# El_Sequencer_Board.net
KiCad netlist of a schematic drawn in EAGLE
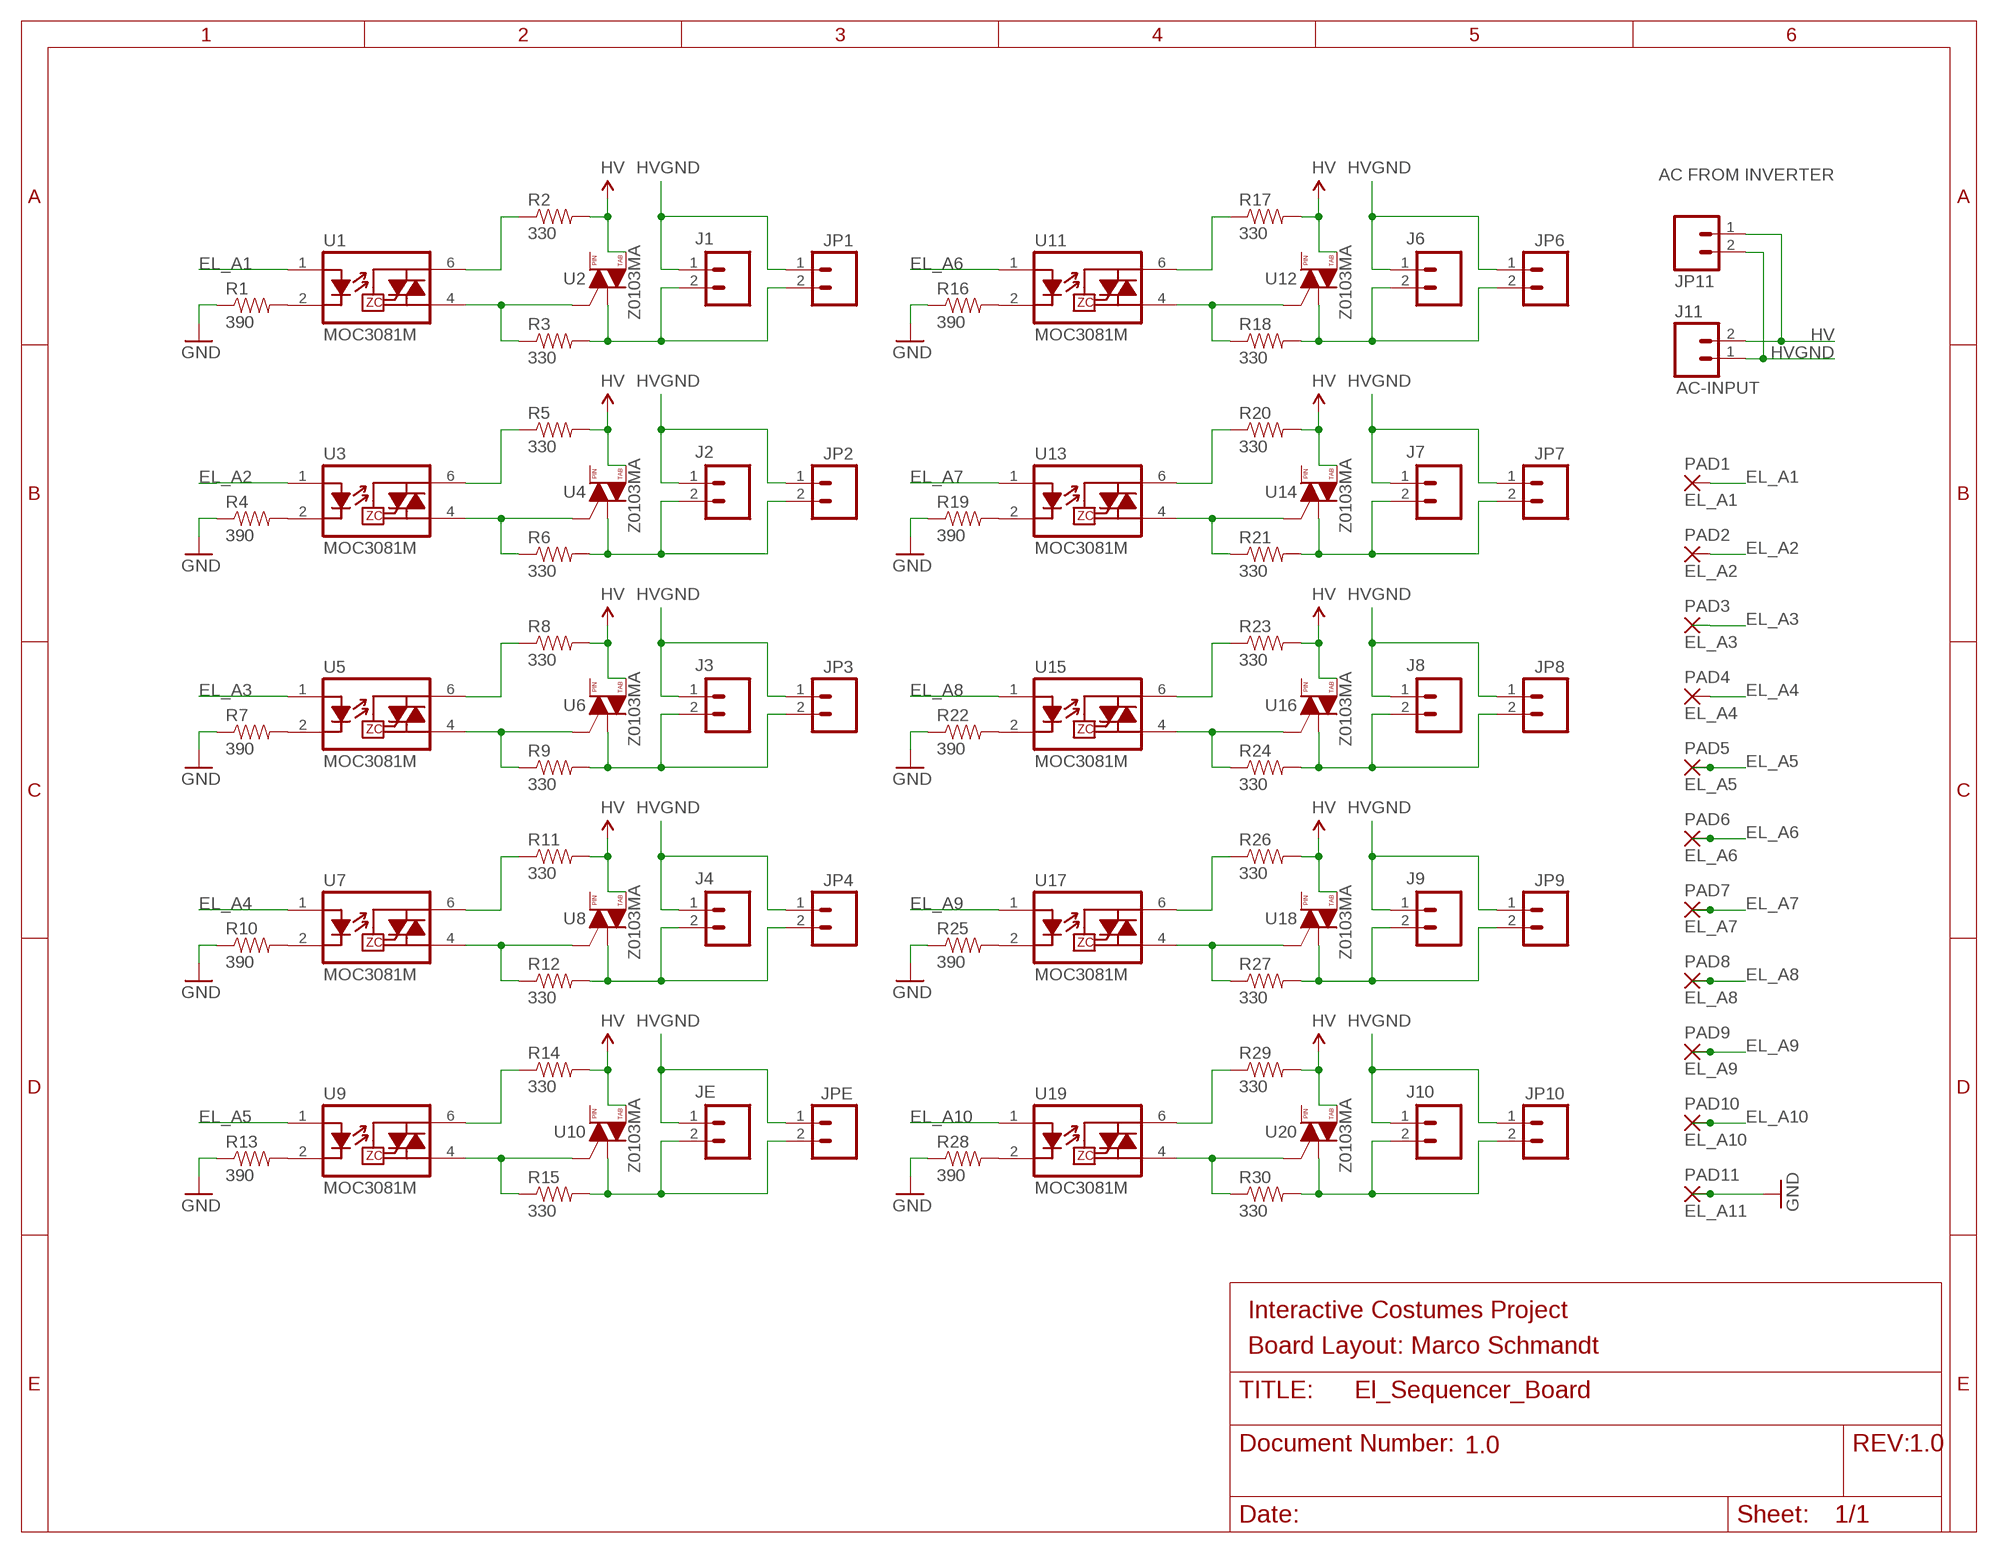
[diagram p0: schematic, sheet 1]

(export (version "E")
  (design (tool "Eeschema 10.0.6"))
  (components
    (comp (ref "J1")
      (value "M02-JST-2MM-SMT")
      (footprint "eagle-import:JST-2-SMD")
      (libsource (lib "eagle-import") (part "M02-JST-2MM-SMT"))
    )
    (comp (ref "J2")
      (value "M02-JST-2MM-SMT")
      (footprint "eagle-import:JST-2-SMD")
      (libsource (lib "eagle-import") (part "M02-JST-2MM-SMT"))
    )
    (comp (ref "J3")
      (value "M02-JST-2MM-SMT")
      (footprint "eagle-import:JST-2-SMD")
      (libsource (lib "eagle-import") (part "M02-JST-2MM-SMT"))
    )
    (comp (ref "J4")
      (value "M02-JST-2MM-SMT")
      (footprint "eagle-import:JST-2-SMD")
      (libsource (lib "eagle-import") (part "M02-JST-2MM-SMT"))
    )
    (comp (ref "J6")
      (value "M02-JST-2MM-SMT")
      (footprint "eagle-import:JST-2-SMD")
      (libsource (lib "eagle-import") (part "M02-JST-2MM-SMT"))
    )
    (comp (ref "J7")
      (value "M02-JST-2MM-SMT")
      (footprint "eagle-import:JST-2-SMD")
      (libsource (lib "eagle-import") (part "M02-JST-2MM-SMT"))
    )
    (comp (ref "J8")
      (value "M02-JST-2MM-SMT")
      (footprint "eagle-import:JST-2-SMD")
      (libsource (lib "eagle-import") (part "M02-JST-2MM-SMT"))
    )
    (comp (ref "J9")
      (value "M02-JST-2MM-SMT")
      (footprint "eagle-import:JST-2-SMD")
      (libsource (lib "eagle-import") (part "M02-JST-2MM-SMT"))
    )
    (comp (ref "J10")
      (value "M02-JST-2MM-SMT")
      (footprint "eagle-import:JST-2-SMD")
      (libsource (lib "eagle-import") (part "M02-JST-2MM-SMT"))
    )
    (comp (ref "J11")
      (value "AC-INPUT")
      (footprint "eagle-import:JST-2-SMD")
      (libsource (lib "eagle-import") (part "M02-JST-2MM-SMT"))
    )
    (comp (ref "JE")
      (value "M02-JST-2MM-SMT")
      (footprint "eagle-import:JST-2-SMD")
      (libsource (lib "eagle-import") (part "M02-JST-2MM-SMT"))
    )
    (comp (ref "JP1")
      (value "M02PTH")
      (footprint "eagle-import:1X02")
      (libsource (lib "eagle-import") (part "M02PTH"))
    )
    (comp (ref "JP2")
      (value "M02PTH")
      (footprint "eagle-import:1X02")
      (libsource (lib "eagle-import") (part "M02PTH"))
    )
    (comp (ref "JP3")
      (value "M02PTH")
      (footprint "eagle-import:1X02")
      (libsource (lib "eagle-import") (part "M02PTH"))
    )
    (comp (ref "JP4")
      (value "M02PTH")
      (footprint "eagle-import:1X02")
      (libsource (lib "eagle-import") (part "M02PTH"))
    )
    (comp (ref "JP6")
      (value "M02PTH")
      (footprint "eagle-import:1X02")
      (libsource (lib "eagle-import") (part "M02PTH"))
    )
    (comp (ref "JP7")
      (value "M02PTH")
      (footprint "eagle-import:1X02")
      (libsource (lib "eagle-import") (part "M02PTH"))
    )
    (comp (ref "JP8")
      (value "M02PTH")
      (footprint "eagle-import:1X02")
      (libsource (lib "eagle-import") (part "M02PTH"))
    )
    (comp (ref "JP9")
      (value "M02PTH")
      (footprint "eagle-import:1X02")
      (libsource (lib "eagle-import") (part "M02PTH"))
    )
    (comp (ref "JP10")
      (value "M02PTH")
      (footprint "eagle-import:1X02")
      (libsource (lib "eagle-import") (part "M02PTH"))
    )
    (comp (ref "JP11")
      (value "M02PTH")
      (footprint "eagle-import:1X02")
      (libsource (lib "eagle-import") (part "M02PTH"))
    )
    (comp (ref "JPE")
      (value "M02PTH")
      (footprint "eagle-import:1X02")
      (libsource (lib "eagle-import") (part "M02PTH"))
    )
    (comp (ref "PAD1")
      (value "EL_A1")
      (footprint "eagle-import:5-2,5")
      (libsource (lib "eagle-import") (part "WIREPADSMD5-2,5"))
    )
    (comp (ref "PAD2")
      (value "EL_A2")
      (footprint "eagle-import:5-2,5")
      (libsource (lib "eagle-import") (part "WIREPADSMD5-2,5"))
    )
    (comp (ref "PAD3")
      (value "EL_A3")
      (footprint "eagle-import:5-2,5")
      (libsource (lib "eagle-import") (part "WIREPADSMD5-2,5"))
    )
    (comp (ref "PAD4")
      (value "EL_A4")
      (footprint "eagle-import:5-2,5")
      (libsource (lib "eagle-import") (part "WIREPADSMD5-2,5"))
    )
    (comp (ref "PAD5")
      (value "EL_A5")
      (footprint "eagle-import:5-2,5")
      (libsource (lib "eagle-import") (part "WIREPADSMD5-2,5"))
    )
    (comp (ref "PAD6")
      (value "EL_A6")
      (footprint "eagle-import:5-2,5")
      (libsource (lib "eagle-import") (part "WIREPADSMD5-2,5"))
    )
    (comp (ref "PAD7")
      (value "EL_A7")
      (footprint "eagle-import:5-2,5")
      (libsource (lib "eagle-import") (part "WIREPADSMD5-2,5"))
    )
    (comp (ref "PAD8")
      (value "EL_A8")
      (footprint "eagle-import:5-2,5")
      (libsource (lib "eagle-import") (part "WIREPADSMD5-2,5"))
    )
    (comp (ref "PAD9")
      (value "EL_A9")
      (footprint "eagle-import:5-2,5")
      (libsource (lib "eagle-import") (part "WIREPADSMD5-2,5"))
    )
    (comp (ref "PAD10")
      (value "EL_A10")
      (footprint "eagle-import:5-2,5")
      (libsource (lib "eagle-import") (part "WIREPADSMD5-2,5"))
    )
    (comp (ref "PAD11")
      (value "EL_A11")
      (footprint "eagle-import:5-2,5")
      (libsource (lib "eagle-import") (part "WIREPADSMD5-2,5"))
    )
    (comp (ref "R1")
      (value "390")
      (footprint "eagle-import:0402-RES")
      (libsource (lib "eagle-import") (part "RESISTOR0402-RES"))
    )
    (comp (ref "R2")
      (value "330")
      (footprint "eagle-import:0603-RES")
      (libsource (lib "eagle-import") (part "RESISTOR0603-RES"))
    )
    (comp (ref "R3")
      (value "330")
      (footprint "eagle-import:0603-RES")
      (libsource (lib "eagle-import") (part "RESISTOR0603-RES"))
    )
    (comp (ref "R4")
      (value "390")
      (footprint "eagle-import:0402-RES")
      (libsource (lib "eagle-import") (part "RESISTOR0402-RES"))
    )
    (comp (ref "R5")
      (value "330")
      (footprint "eagle-import:0603-RES")
      (libsource (lib "eagle-import") (part "RESISTOR0603-RES"))
    )
    (comp (ref "R6")
      (value "330")
      (footprint "eagle-import:0603-RES")
      (libsource (lib "eagle-import") (part "RESISTOR0603-RES"))
    )
    (comp (ref "R7")
      (value "390")
      (footprint "eagle-import:0402-RES")
      (libsource (lib "eagle-import") (part "RESISTOR0402-RES"))
    )
    (comp (ref "R8")
      (value "330")
      (footprint "eagle-import:0603-RES")
      (libsource (lib "eagle-import") (part "RESISTOR0603-RES"))
    )
    (comp (ref "R9")
      (value "330")
      (footprint "eagle-import:0603-RES")
      (libsource (lib "eagle-import") (part "RESISTOR0603-RES"))
    )
    (comp (ref "R10")
      (value "390")
      (footprint "eagle-import:0402-RES")
      (libsource (lib "eagle-import") (part "RESISTOR0402-RES"))
    )
    (comp (ref "R11")
      (value "330")
      (footprint "eagle-import:0603-RES")
      (libsource (lib "eagle-import") (part "RESISTOR0603-RES"))
    )
    (comp (ref "R12")
      (value "330")
      (footprint "eagle-import:0603-RES")
      (libsource (lib "eagle-import") (part "RESISTOR0603-RES"))
    )
    (comp (ref "R13")
      (value "390")
      (footprint "eagle-import:0402-RES")
      (libsource (lib "eagle-import") (part "RESISTOR0402-RES"))
    )
    (comp (ref "R14")
      (value "330")
      (footprint "eagle-import:0603-RES")
      (libsource (lib "eagle-import") (part "RESISTOR0603-RES"))
    )
    (comp (ref "R15")
      (value "330")
      (footprint "eagle-import:0603-RES")
      (libsource (lib "eagle-import") (part "RESISTOR0603-RES"))
    )
    (comp (ref "R16")
      (value "390")
      (footprint "eagle-import:0402-RES")
      (libsource (lib "eagle-import") (part "RESISTOR0402-RES"))
    )
    (comp (ref "R17")
      (value "330")
      (footprint "eagle-import:0603-RES")
      (libsource (lib "eagle-import") (part "RESISTOR0603-RES"))
    )
    (comp (ref "R18")
      (value "330")
      (footprint "eagle-import:0603-RES")
      (libsource (lib "eagle-import") (part "RESISTOR0603-RES"))
    )
    (comp (ref "R19")
      (value "390")
      (footprint "eagle-import:0402-RES")
      (libsource (lib "eagle-import") (part "RESISTOR0402-RES"))
    )
    (comp (ref "R20")
      (value "330")
      (footprint "eagle-import:0603-RES")
      (libsource (lib "eagle-import") (part "RESISTOR0603-RES"))
    )
    (comp (ref "R21")
      (value "330")
      (footprint "eagle-import:0603-RES")
      (libsource (lib "eagle-import") (part "RESISTOR0603-RES"))
    )
    (comp (ref "R22")
      (value "390")
      (footprint "eagle-import:0402-RES")
      (libsource (lib "eagle-import") (part "RESISTOR0402-RES"))
    )
    (comp (ref "R23")
      (value "330")
      (footprint "eagle-import:0603-RES")
      (libsource (lib "eagle-import") (part "RESISTOR0603-RES"))
    )
    (comp (ref "R24")
      (value "330")
      (footprint "eagle-import:0603-RES")
      (libsource (lib "eagle-import") (part "RESISTOR0603-RES"))
    )
    (comp (ref "R25")
      (value "390")
      (footprint "eagle-import:0402-RES")
      (libsource (lib "eagle-import") (part "RESISTOR0402-RES"))
    )
    (comp (ref "R26")
      (value "330")
      (footprint "eagle-import:0603-RES")
      (libsource (lib "eagle-import") (part "RESISTOR0603-RES"))
    )
    (comp (ref "R27")
      (value "330")
      (footprint "eagle-import:0603-RES")
      (libsource (lib "eagle-import") (part "RESISTOR0603-RES"))
    )
    (comp (ref "R28")
      (value "390")
      (footprint "eagle-import:0402-RES")
      (libsource (lib "eagle-import") (part "RESISTOR0402-RES"))
    )
    (comp (ref "R29")
      (value "330")
      (footprint "eagle-import:0603-RES")
      (libsource (lib "eagle-import") (part "RESISTOR0603-RES"))
    )
    (comp (ref "R30")
      (value "330")
      (footprint "eagle-import:0603-RES")
      (libsource (lib "eagle-import") (part "RESISTOR0603-RES"))
    )
    (comp (ref "U1")
      (value "MOC3081M")
      (footprint "eagle-import:DIP8SMD")
      (libsource (lib "eagle-import") (part "MOC3063S"))
    )
    (comp (ref "U2")
      (value "Z0103MA")
      (footprint "eagle-import:SOT223")
      (libsource (lib "eagle-import") (part "TRIACSMD"))
    )
    (comp (ref "U3")
      (value "MOC3081M")
      (footprint "eagle-import:DIP8SMD")
      (libsource (lib "eagle-import") (part "MOC3063S"))
    )
    (comp (ref "U4")
      (value "Z0103MA")
      (footprint "eagle-import:SOT223")
      (libsource (lib "eagle-import") (part "TRIACSMD"))
    )
    (comp (ref "U5")
      (value "MOC3081M")
      (footprint "eagle-import:DIP8SMD")
      (libsource (lib "eagle-import") (part "MOC3063S"))
    )
    (comp (ref "U6")
      (value "Z0103MA")
      (footprint "eagle-import:SOT223")
      (libsource (lib "eagle-import") (part "TRIACSMD"))
    )
    (comp (ref "U7")
      (value "MOC3081M")
      (footprint "eagle-import:DIP8SMD")
      (libsource (lib "eagle-import") (part "MOC3063S"))
    )
    (comp (ref "U8")
      (value "Z0103MA")
      (footprint "eagle-import:SOT223")
      (libsource (lib "eagle-import") (part "TRIACSMD"))
    )
    (comp (ref "U9")
      (value "MOC3081M")
      (footprint "eagle-import:DIP8SMD")
      (libsource (lib "eagle-import") (part "MOC3063S"))
    )
    (comp (ref "U10")
      (value "Z0103MA")
      (footprint "eagle-import:SOT223")
      (libsource (lib "eagle-import") (part "TRIACSMD"))
    )
    (comp (ref "U11")
      (value "MOC3081M")
      (footprint "eagle-import:DIP8SMD")
      (libsource (lib "eagle-import") (part "MOC3063S"))
    )
    (comp (ref "U12")
      (value "Z0103MA")
      (footprint "eagle-import:SOT223")
      (libsource (lib "eagle-import") (part "TRIACSMD"))
    )
    (comp (ref "U13")
      (value "MOC3081M")
      (footprint "eagle-import:DIP8SMD")
      (libsource (lib "eagle-import") (part "MOC3063S"))
    )
    (comp (ref "U14")
      (value "Z0103MA")
      (footprint "eagle-import:SOT223")
      (libsource (lib "eagle-import") (part "TRIACSMD"))
    )
    (comp (ref "U15")
      (value "MOC3081M")
      (footprint "eagle-import:DIP8SMD")
      (libsource (lib "eagle-import") (part "MOC3063S"))
    )
    (comp (ref "U16")
      (value "Z0103MA")
      (footprint "eagle-import:SOT223")
      (libsource (lib "eagle-import") (part "TRIACSMD"))
    )
    (comp (ref "U17")
      (value "MOC3081M")
      (footprint "eagle-import:DIP8SMD")
      (libsource (lib "eagle-import") (part "MOC3063S"))
    )
    (comp (ref "U18")
      (value "Z0103MA")
      (footprint "eagle-import:SOT223")
      (libsource (lib "eagle-import") (part "TRIACSMD"))
    )
    (comp (ref "U19")
      (value "MOC3081M")
      (footprint "eagle-import:DIP8SMD")
      (libsource (lib "eagle-import") (part "MOC3063S"))
    )
    (comp (ref "U20")
      (value "Z0103MA")
      (footprint "eagle-import:SOT223")
      (libsource (lib "eagle-import") (part "TRIACSMD"))
    )
  )
  (nets
    (net (code "1") (name "/EL_A1") (class "Default")
      (node (ref "PAD1") (pin "1") (pinfunction "P_1") (pintype "passive"))
      (node (ref "U1") (pin "1") (pinfunction "A_1") (pintype "bidirectional"))
    )
    (net (code "2") (name "/EL_A2") (class "Default")
      (node (ref "PAD2") (pin "1") (pinfunction "P_1") (pintype "passive"))
      (node (ref "U3") (pin "1") (pinfunction "A_1") (pintype "bidirectional"))
    )
    (net (code "3") (name "/EL_A3") (class "Default")
      (node (ref "PAD3") (pin "1") (pinfunction "P_1") (pintype "passive"))
      (node (ref "U5") (pin "1") (pinfunction "A_1") (pintype "bidirectional"))
    )
    (net (code "4") (name "/EL_A4") (class "Default")
      (node (ref "PAD4") (pin "1") (pinfunction "P_1") (pintype "passive"))
      (node (ref "U7") (pin "1") (pinfunction "A_1") (pintype "bidirectional"))
    )
    (net (code "5") (name "/EL_A5") (class "Default")
      (node (ref "PAD5") (pin "1") (pinfunction "P_1") (pintype "passive"))
      (node (ref "U9") (pin "1") (pinfunction "A_1") (pintype "bidirectional"))
    )
    (net (code "6") (name "/EL_A6") (class "Default")
      (node (ref "PAD6") (pin "1") (pinfunction "P_1") (pintype "passive"))
      (node (ref "U11") (pin "1") (pinfunction "A_1") (pintype "bidirectional"))
    )
    (net (code "7") (name "/EL_A7") (class "Default")
      (node (ref "PAD7") (pin "1") (pinfunction "P_1") (pintype "passive"))
      (node (ref "U13") (pin "1") (pinfunction "A_1") (pintype "bidirectional"))
    )
    (net (code "8") (name "/EL_A8") (class "Default")
      (node (ref "PAD8") (pin "1") (pinfunction "P_1") (pintype "passive"))
      (node (ref "U15") (pin "1") (pinfunction "A_1") (pintype "bidirectional"))
    )
    (net (code "9") (name "/EL_A9") (class "Default")
      (node (ref "PAD9") (pin "1") (pinfunction "P_1") (pintype "passive"))
      (node (ref "U17") (pin "1") (pinfunction "A_1") (pintype "bidirectional"))
    )
    (net (code "10") (name "/EL_A10") (class "Default")
      (node (ref "PAD10") (pin "1") (pinfunction "P_1") (pintype "passive"))
      (node (ref "U19") (pin "1") (pinfunction "A_1") (pintype "bidirectional"))
    )
    (net (code "11") (name "/HVGND") (class "Default")
      (node (ref "J1") (pin "1") (pinfunction "1_1") (pintype "passive"))
      (node (ref "J10") (pin "1") (pinfunction "1_1") (pintype "passive"))
      (node (ref "J11") (pin "1") (pinfunction "1_1") (pintype "passive"))
      (node (ref "J2") (pin "1") (pinfunction "1_1") (pintype "passive"))
      (node (ref "J3") (pin "1") (pinfunction "1_1") (pintype "passive"))
      (node (ref "J4") (pin "1") (pinfunction "1_1") (pintype "passive"))
      (node (ref "J6") (pin "1") (pinfunction "1_1") (pintype "passive"))
      (node (ref "J7") (pin "1") (pinfunction "1_1") (pintype "passive"))
      (node (ref "J8") (pin "1") (pinfunction "1_1") (pintype "passive"))
      (node (ref "J9") (pin "1") (pinfunction "1_1") (pintype "passive"))
      (node (ref "JE") (pin "1") (pinfunction "1_1") (pintype "passive"))
      (node (ref "JP1") (pin "1") (pinfunction "1_1") (pintype "passive"))
      (node (ref "JP10") (pin "1") (pinfunction "1_1") (pintype "passive"))
      (node (ref "JP11") (pin "2") (pinfunction "2_2") (pintype "passive"))
      (node (ref "JP2") (pin "1") (pinfunction "1_1") (pintype "passive"))
      (node (ref "JP3") (pin "1") (pinfunction "1_1") (pintype "passive"))
      (node (ref "JP4") (pin "1") (pinfunction "1_1") (pintype "passive"))
      (node (ref "JP6") (pin "1") (pinfunction "1_1") (pintype "passive"))
      (node (ref "JP7") (pin "1") (pinfunction "1_1") (pintype "passive"))
      (node (ref "JP8") (pin "1") (pinfunction "1_1") (pintype "passive"))
      (node (ref "JP9") (pin "1") (pinfunction "1_1") (pintype "passive"))
      (node (ref "JPE") (pin "1") (pinfunction "1_1") (pintype "passive"))
    )
    (net (code "12") (name "GND") (class "Default")
      (node (ref "PAD11") (pin "1") (pinfunction "P_1") (pintype "passive"))
      (node (ref "R1") (pin "1") (pinfunction "1_1") (pintype "passive"))
      (node (ref "R10") (pin "1") (pinfunction "1_1") (pintype "passive"))
      (node (ref "R13") (pin "1") (pinfunction "1_1") (pintype "passive"))
      (node (ref "R16") (pin "1") (pinfunction "1_1") (pintype "passive"))
      (node (ref "R19") (pin "1") (pinfunction "1_1") (pintype "passive"))
      (node (ref "R22") (pin "1") (pinfunction "1_1") (pintype "passive"))
      (node (ref "R25") (pin "1") (pinfunction "1_1") (pintype "passive"))
      (node (ref "R28") (pin "1") (pinfunction "1_1") (pintype "passive"))
      (node (ref "R4") (pin "1") (pinfunction "1_1") (pintype "passive"))
      (node (ref "R7") (pin "1") (pinfunction "1_1") (pintype "passive"))
    )
    (net (code "13") (name "HV") (class "Default")
      (node (ref "J11") (pin "2") (pinfunction "2_2") (pintype "passive"))
      (node (ref "JP11") (pin "1") (pinfunction "1_1") (pintype "passive"))
      (node (ref "R11") (pin "2") (pinfunction "2_2") (pintype "passive"))
      (node (ref "R14") (pin "2") (pinfunction "2_2") (pintype "passive"))
      (node (ref "R17") (pin "2") (pinfunction "2_2") (pintype "passive"))
      (node (ref "R2") (pin "2") (pinfunction "2_2") (pintype "passive"))
      (node (ref "R20") (pin "2") (pinfunction "2_2") (pintype "passive"))
      (node (ref "R23") (pin "2") (pinfunction "2_2") (pintype "passive"))
      (node (ref "R26") (pin "2") (pinfunction "2_2") (pintype "passive"))
      (node (ref "R29") (pin "2") (pinfunction "2_2") (pintype "passive"))
      (node (ref "R5") (pin "2") (pinfunction "2_2") (pintype "passive"))
      (node (ref "R8") (pin "2") (pinfunction "2_2") (pintype "passive"))
      (node (ref "U10") (pin "4") (pinfunction "T2_4") (pintype "passive"))
      (node (ref "U12") (pin "4") (pinfunction "T2_4") (pintype "passive"))
      (node (ref "U14") (pin "4") (pinfunction "T2_4") (pintype "passive"))
      (node (ref "U16") (pin "4") (pinfunction "T2_4") (pintype "passive"))
      (node (ref "U18") (pin "4") (pinfunction "T2_4") (pintype "passive"))
      (node (ref "U2") (pin "4") (pinfunction "T2_4") (pintype "passive"))
      (node (ref "U20") (pin "4") (pinfunction "T2_4") (pintype "passive"))
      (node (ref "U4") (pin "4") (pinfunction "T2_4") (pintype "passive"))
      (node (ref "U6") (pin "4") (pinfunction "T2_4") (pintype "passive"))
      (node (ref "U8") (pin "4") (pinfunction "T2_4") (pintype "passive"))
    )
    (net (code "14") (name "Net-(U1-K)") (class "Default")
      (node (ref "R1") (pin "2") (pinfunction "2_2") (pintype "passive"))
      (node (ref "U1") (pin "2") (pinfunction "K_2") (pintype "bidirectional"))
    )
    (net (code "15") (name "Net-(U1-T1)") (class "Default")
      (node (ref "R2") (pin "1") (pinfunction "1_1") (pintype "passive"))
      (node (ref "U1") (pin "6") (pinfunction "T1_6") (pintype "bidirectional"))
    )
    (net (code "16") (name "Net-(U1-T2)") (class "Default")
      (node (ref "R3") (pin "1") (pinfunction "1_1") (pintype "passive"))
      (node (ref "U1") (pin "4") (pinfunction "T2_4") (pintype "bidirectional"))
      (node (ref "U2") (pin "3") (pinfunction "G_3") (pintype "bidirectional"))
    )
    (net (code "17") (name "Net-(U2-T1)") (class "Default")
      (node (ref "J1") (pin "2") (pinfunction "2_2") (pintype "passive"))
      (node (ref "JP1") (pin "2") (pinfunction "2_2") (pintype "passive"))
      (node (ref "R3") (pin "2") (pinfunction "2_2") (pintype "passive"))
      (node (ref "U2") (pin "1") (pinfunction "T1_1") (pintype "bidirectional"))
    )
    (net (code "18") (name "Net-(U3-K)") (class "Default")
      (node (ref "R4") (pin "2") (pinfunction "2_2") (pintype "passive"))
      (node (ref "U3") (pin "2") (pinfunction "K_2") (pintype "bidirectional"))
    )
    (net (code "19") (name "Net-(U3-T1)") (class "Default")
      (node (ref "R5") (pin "1") (pinfunction "1_1") (pintype "passive"))
      (node (ref "U3") (pin "6") (pinfunction "T1_6") (pintype "bidirectional"))
    )
    (net (code "20") (name "Net-(U3-T2)") (class "Default")
      (node (ref "R6") (pin "1") (pinfunction "1_1") (pintype "passive"))
      (node (ref "U3") (pin "4") (pinfunction "T2_4") (pintype "bidirectional"))
      (node (ref "U4") (pin "3") (pinfunction "G_3") (pintype "bidirectional"))
    )
    (net (code "21") (name "Net-(U4-T1)") (class "Default")
      (node (ref "J2") (pin "2") (pinfunction "2_2") (pintype "passive"))
      (node (ref "JP2") (pin "2") (pinfunction "2_2") (pintype "passive"))
      (node (ref "R6") (pin "2") (pinfunction "2_2") (pintype "passive"))
      (node (ref "U4") (pin "1") (pinfunction "T1_1") (pintype "bidirectional"))
    )
    (net (code "22") (name "Net-(U5-K)") (class "Default")
      (node (ref "R7") (pin "2") (pinfunction "2_2") (pintype "passive"))
      (node (ref "U5") (pin "2") (pinfunction "K_2") (pintype "bidirectional"))
    )
    (net (code "23") (name "Net-(U5-T1)") (class "Default")
      (node (ref "R8") (pin "1") (pinfunction "1_1") (pintype "passive"))
      (node (ref "U5") (pin "6") (pinfunction "T1_6") (pintype "bidirectional"))
    )
    (net (code "24") (name "Net-(U5-T2)") (class "Default")
      (node (ref "R9") (pin "1") (pinfunction "1_1") (pintype "passive"))
      (node (ref "U5") (pin "4") (pinfunction "T2_4") (pintype "bidirectional"))
      (node (ref "U6") (pin "3") (pinfunction "G_3") (pintype "bidirectional"))
    )
    (net (code "25") (name "Net-(U6-T1)") (class "Default")
      (node (ref "J3") (pin "2") (pinfunction "2_2") (pintype "passive"))
      (node (ref "JP3") (pin "2") (pinfunction "2_2") (pintype "passive"))
      (node (ref "R9") (pin "2") (pinfunction "2_2") (pintype "passive"))
      (node (ref "U6") (pin "1") (pinfunction "T1_1") (pintype "bidirectional"))
    )
    (net (code "26") (name "Net-(U7-K)") (class "Default")
      (node (ref "R10") (pin "2") (pinfunction "2_2") (pintype "passive"))
      (node (ref "U7") (pin "2") (pinfunction "K_2") (pintype "bidirectional"))
    )
    (net (code "27") (name "Net-(U7-T1)") (class "Default")
      (node (ref "R11") (pin "1") (pinfunction "1_1") (pintype "passive"))
      (node (ref "U7") (pin "6") (pinfunction "T1_6") (pintype "bidirectional"))
    )
    (net (code "28") (name "Net-(U7-T2)") (class "Default")
      (node (ref "R12") (pin "1") (pinfunction "1_1") (pintype "passive"))
      (node (ref "U7") (pin "4") (pinfunction "T2_4") (pintype "bidirectional"))
      (node (ref "U8") (pin "3") (pinfunction "G_3") (pintype "bidirectional"))
    )
    (net (code "29") (name "Net-(U8-T1)") (class "Default")
      (node (ref "J4") (pin "2") (pinfunction "2_2") (pintype "passive"))
      (node (ref "JP4") (pin "2") (pinfunction "2_2") (pintype "passive"))
      (node (ref "R12") (pin "2") (pinfunction "2_2") (pintype "passive"))
      (node (ref "U8") (pin "1") (pinfunction "T1_1") (pintype "bidirectional"))
    )
    (net (code "30") (name "Net-(U9-K)") (class "Default")
      (node (ref "R13") (pin "2") (pinfunction "2_2") (pintype "passive"))
      (node (ref "U9") (pin "2") (pinfunction "K_2") (pintype "bidirectional"))
    )
    (net (code "31") (name "Net-(U9-T1)") (class "Default")
      (node (ref "R14") (pin "1") (pinfunction "1_1") (pintype "passive"))
      (node (ref "U9") (pin "6") (pinfunction "T1_6") (pintype "bidirectional"))
    )
    (net (code "32") (name "Net-(U10-G)") (class "Default")
      (node (ref "R15") (pin "1") (pinfunction "1_1") (pintype "passive"))
      (node (ref "U10") (pin "3") (pinfunction "G_3") (pintype "bidirectional"))
      (node (ref "U9") (pin "4") (pinfunction "T2_4") (pintype "bidirectional"))
    )
    (net (code "33") (name "Net-(U10-T1)") (class "Default")
      (node (ref "JE") (pin "2") (pinfunction "2_2") (pintype "passive"))
      (node (ref "JPE") (pin "2") (pinfunction "2_2") (pintype "passive"))
      (node (ref "R15") (pin "2") (pinfunction "2_2") (pintype "passive"))
      (node (ref "U10") (pin "1") (pinfunction "T1_1") (pintype "bidirectional"))
    )
    (net (code "34") (name "Net-(U11-K)") (class "Default")
      (node (ref "R16") (pin "2") (pinfunction "2_2") (pintype "passive"))
      (node (ref "U11") (pin "2") (pinfunction "K_2") (pintype "bidirectional"))
    )
    (net (code "35") (name "Net-(U11-T1)") (class "Default")
      (node (ref "R17") (pin "1") (pinfunction "1_1") (pintype "passive"))
      (node (ref "U11") (pin "6") (pinfunction "T1_6") (pintype "bidirectional"))
    )
    (net (code "36") (name "Net-(U11-T2)") (class "Default")
      (node (ref "R18") (pin "1") (pinfunction "1_1") (pintype "passive"))
      (node (ref "U11") (pin "4") (pinfunction "T2_4") (pintype "bidirectional"))
      (node (ref "U12") (pin "3") (pinfunction "G_3") (pintype "bidirectional"))
    )
    (net (code "37") (name "Net-(U12-T1)") (class "Default")
      (node (ref "J6") (pin "2") (pinfunction "2_2") (pintype "passive"))
      (node (ref "JP6") (pin "2") (pinfunction "2_2") (pintype "passive"))
      (node (ref "R18") (pin "2") (pinfunction "2_2") (pintype "passive"))
      (node (ref "U12") (pin "1") (pinfunction "T1_1") (pintype "bidirectional"))
    )
    (net (code "38") (name "Net-(U13-K)") (class "Default")
      (node (ref "R19") (pin "2") (pinfunction "2_2") (pintype "passive"))
      (node (ref "U13") (pin "2") (pinfunction "K_2") (pintype "bidirectional"))
    )
    (net (code "39") (name "Net-(U13-T1)") (class "Default")
      (node (ref "R20") (pin "1") (pinfunction "1_1") (pintype "passive"))
      (node (ref "U13") (pin "6") (pinfunction "T1_6") (pintype "bidirectional"))
    )
    (net (code "40") (name "Net-(U13-T2)") (class "Default")
      (node (ref "R21") (pin "1") (pinfunction "1_1") (pintype "passive"))
      (node (ref "U13") (pin "4") (pinfunction "T2_4") (pintype "bidirectional"))
      (node (ref "U14") (pin "3") (pinfunction "G_3") (pintype "bidirectional"))
    )
    (net (code "41") (name "Net-(U14-T1)") (class "Default")
      (node (ref "J7") (pin "2") (pinfunction "2_2") (pintype "passive"))
      (node (ref "JP7") (pin "2") (pinfunction "2_2") (pintype "passive"))
      (node (ref "R21") (pin "2") (pinfunction "2_2") (pintype "passive"))
      (node (ref "U14") (pin "1") (pinfunction "T1_1") (pintype "bidirectional"))
    )
    (net (code "42") (name "Net-(U15-K)") (class "Default")
      (node (ref "R22") (pin "2") (pinfunction "2_2") (pintype "passive"))
      (node (ref "U15") (pin "2") (pinfunction "K_2") (pintype "bidirectional"))
    )
    (net (code "43") (name "Net-(U15-T1)") (class "Default")
      (node (ref "R23") (pin "1") (pinfunction "1_1") (pintype "passive"))
      (node (ref "U15") (pin "6") (pinfunction "T1_6") (pintype "bidirectional"))
    )
    (net (code "44") (name "Net-(U15-T2)") (class "Default")
      (node (ref "R24") (pin "1") (pinfunction "1_1") (pintype "passive"))
      (node (ref "U15") (pin "4") (pinfunction "T2_4") (pintype "bidirectional"))
      (node (ref "U16") (pin "3") (pinfunction "G_3") (pintype "bidirectional"))
    )
    (net (code "45") (name "Net-(U16-T1)") (class "Default")
      (node (ref "J8") (pin "2") (pinfunction "2_2") (pintype "passive"))
      (node (ref "JP8") (pin "2") (pinfunction "2_2") (pintype "passive"))
      (node (ref "R24") (pin "2") (pinfunction "2_2") (pintype "passive"))
      (node (ref "U16") (pin "1") (pinfunction "T1_1") (pintype "bidirectional"))
    )
    (net (code "46") (name "Net-(U17-K)") (class "Default")
      (node (ref "R25") (pin "2") (pinfunction "2_2") (pintype "passive"))
      (node (ref "U17") (pin "2") (pinfunction "K_2") (pintype "bidirectional"))
    )
    (net (code "47") (name "Net-(U17-T1)") (class "Default")
      (node (ref "R26") (pin "1") (pinfunction "1_1") (pintype "passive"))
      (node (ref "U17") (pin "6") (pinfunction "T1_6") (pintype "bidirectional"))
    )
    (net (code "48") (name "Net-(U17-T2)") (class "Default")
      (node (ref "R27") (pin "1") (pinfunction "1_1") (pintype "passive"))
      (node (ref "U17") (pin "4") (pinfunction "T2_4") (pintype "bidirectional"))
      (node (ref "U18") (pin "3") (pinfunction "G_3") (pintype "bidirectional"))
    )
    (net (code "49") (name "Net-(U18-T1)") (class "Default")
      (node (ref "J9") (pin "2") (pinfunction "2_2") (pintype "passive"))
      (node (ref "JP9") (pin "2") (pinfunction "2_2") (pintype "passive"))
      (node (ref "R27") (pin "2") (pinfunction "2_2") (pintype "passive"))
      (node (ref "U18") (pin "1") (pinfunction "T1_1") (pintype "bidirectional"))
    )
    (net (code "50") (name "Net-(U19-K)") (class "Default")
      (node (ref "R28") (pin "2") (pinfunction "2_2") (pintype "passive"))
      (node (ref "U19") (pin "2") (pinfunction "K_2") (pintype "bidirectional"))
    )
    (net (code "51") (name "Net-(U19-T1)") (class "Default")
      (node (ref "R29") (pin "1") (pinfunction "1_1") (pintype "passive"))
      (node (ref "U19") (pin "6") (pinfunction "T1_6") (pintype "bidirectional"))
    )
    (net (code "52") (name "Net-(U19-T2)") (class "Default")
      (node (ref "R30") (pin "1") (pinfunction "1_1") (pintype "passive"))
      (node (ref "U19") (pin "4") (pinfunction "T2_4") (pintype "bidirectional"))
      (node (ref "U20") (pin "3") (pinfunction "G_3") (pintype "bidirectional"))
    )
    (net (code "53") (name "Net-(U20-T1)") (class "Default")
      (node (ref "J10") (pin "2") (pinfunction "2_2") (pintype "passive"))
      (node (ref "JP10") (pin "2") (pinfunction "2_2") (pintype "passive"))
      (node (ref "R30") (pin "2") (pinfunction "2_2") (pintype "passive"))
      (node (ref "U20") (pin "1") (pinfunction "T1_1") (pintype "bidirectional"))
    )
    (net (code "54") (name "unconnected-(U2-T2-Pad2)") (class "Default")
      (node (ref "U2") (pin "2") (pinfunction "T2_2") (pintype "passive"))
    )
    (net (code "55") (name "unconnected-(U4-T2-Pad2)") (class "Default")
      (node (ref "U4") (pin "2") (pinfunction "T2_2") (pintype "passive"))
    )
    (net (code "56") (name "unconnected-(U6-T2-Pad2)") (class "Default")
      (node (ref "U6") (pin "2") (pinfunction "T2_2") (pintype "passive"))
    )
    (net (code "57") (name "unconnected-(U8-T2-Pad2)") (class "Default")
      (node (ref "U8") (pin "2") (pinfunction "T2_2") (pintype "passive"))
    )
    (net (code "58") (name "unconnected-(U10-T2-Pad2)") (class "Default")
      (node (ref "U10") (pin "2") (pinfunction "T2_2") (pintype "passive"))
    )
    (net (code "59") (name "unconnected-(U12-T2-Pad2)") (class "Default")
      (node (ref "U12") (pin "2") (pinfunction "T2_2") (pintype "passive"))
    )
    (net (code "60") (name "unconnected-(U14-T2-Pad2)") (class "Default")
      (node (ref "U14") (pin "2") (pinfunction "T2_2") (pintype "passive"))
    )
    (net (code "61") (name "unconnected-(U16-T2-Pad2)") (class "Default")
      (node (ref "U16") (pin "2") (pinfunction "T2_2") (pintype "passive"))
    )
    (net (code "62") (name "unconnected-(U18-T2-Pad2)") (class "Default")
      (node (ref "U18") (pin "2") (pinfunction "T2_2") (pintype "passive"))
    )
    (net (code "63") (name "unconnected-(U20-T2-Pad2)") (class "Default")
      (node (ref "U20") (pin "2") (pinfunction "T2_2") (pintype "passive"))
    )
  )
)
